# leo_BMS.net
KiCad netlist of a schematic drawn in Altium Designer
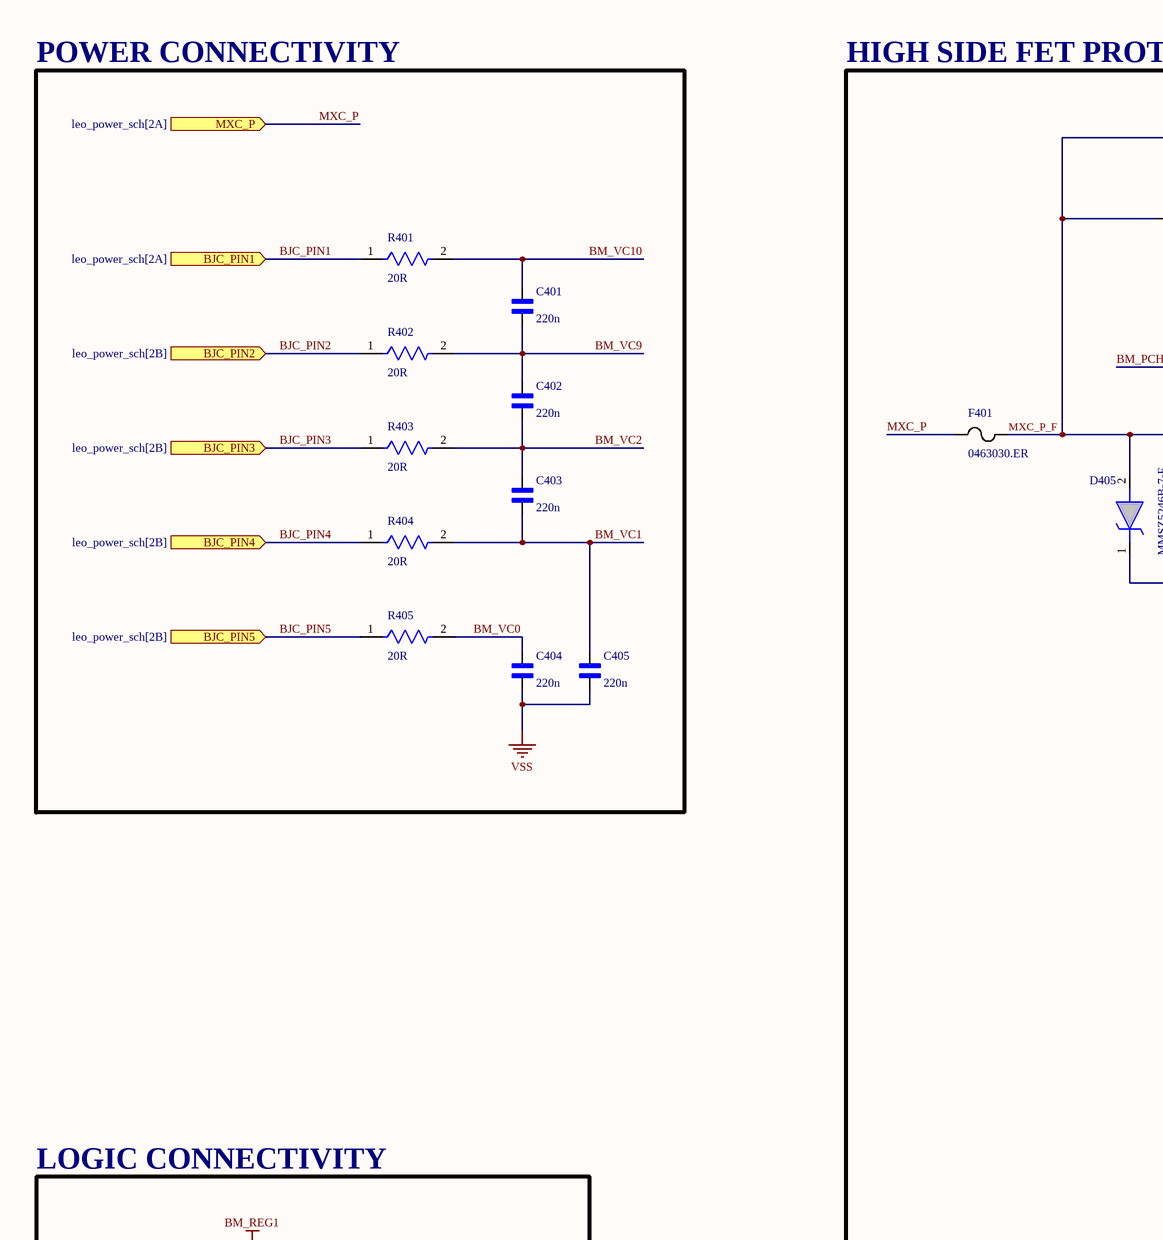
[diagram p0: leo_BMS.SchDoc, top left]
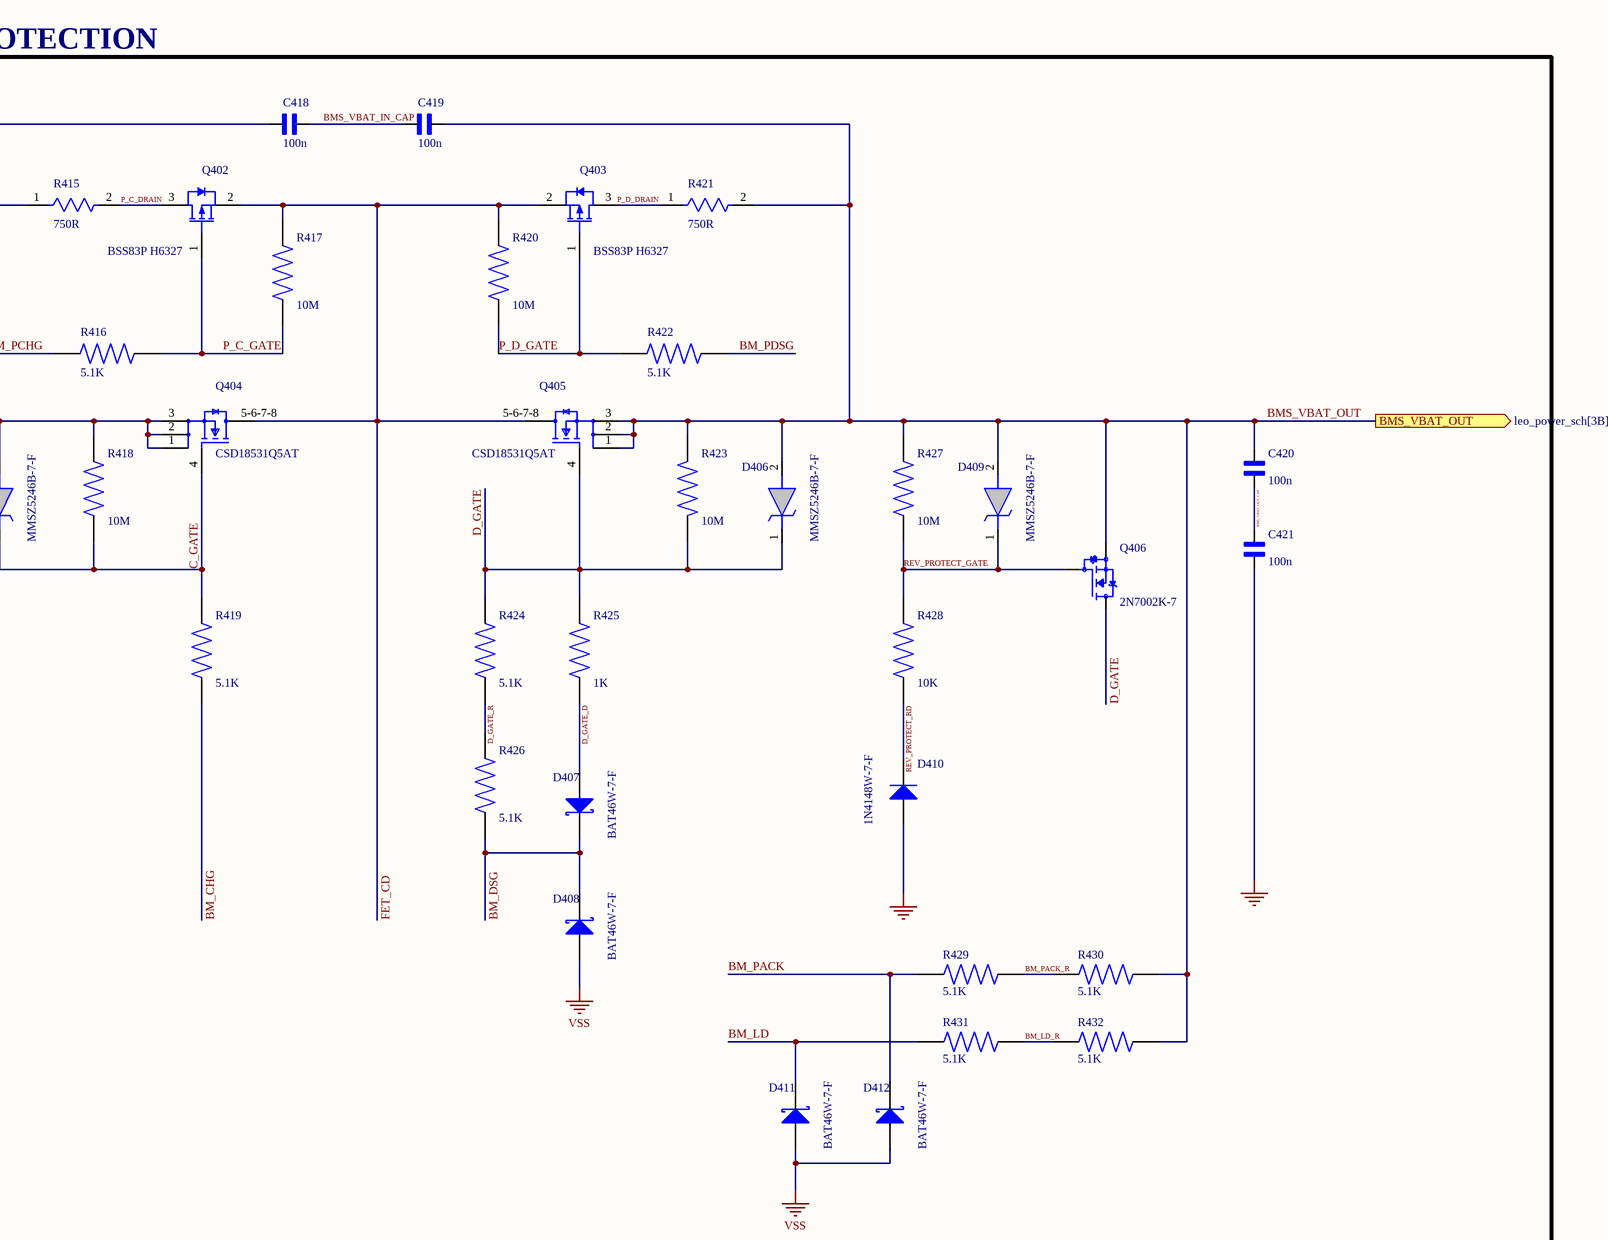
[diagram p1: leo_BMS.SchDoc, top right]
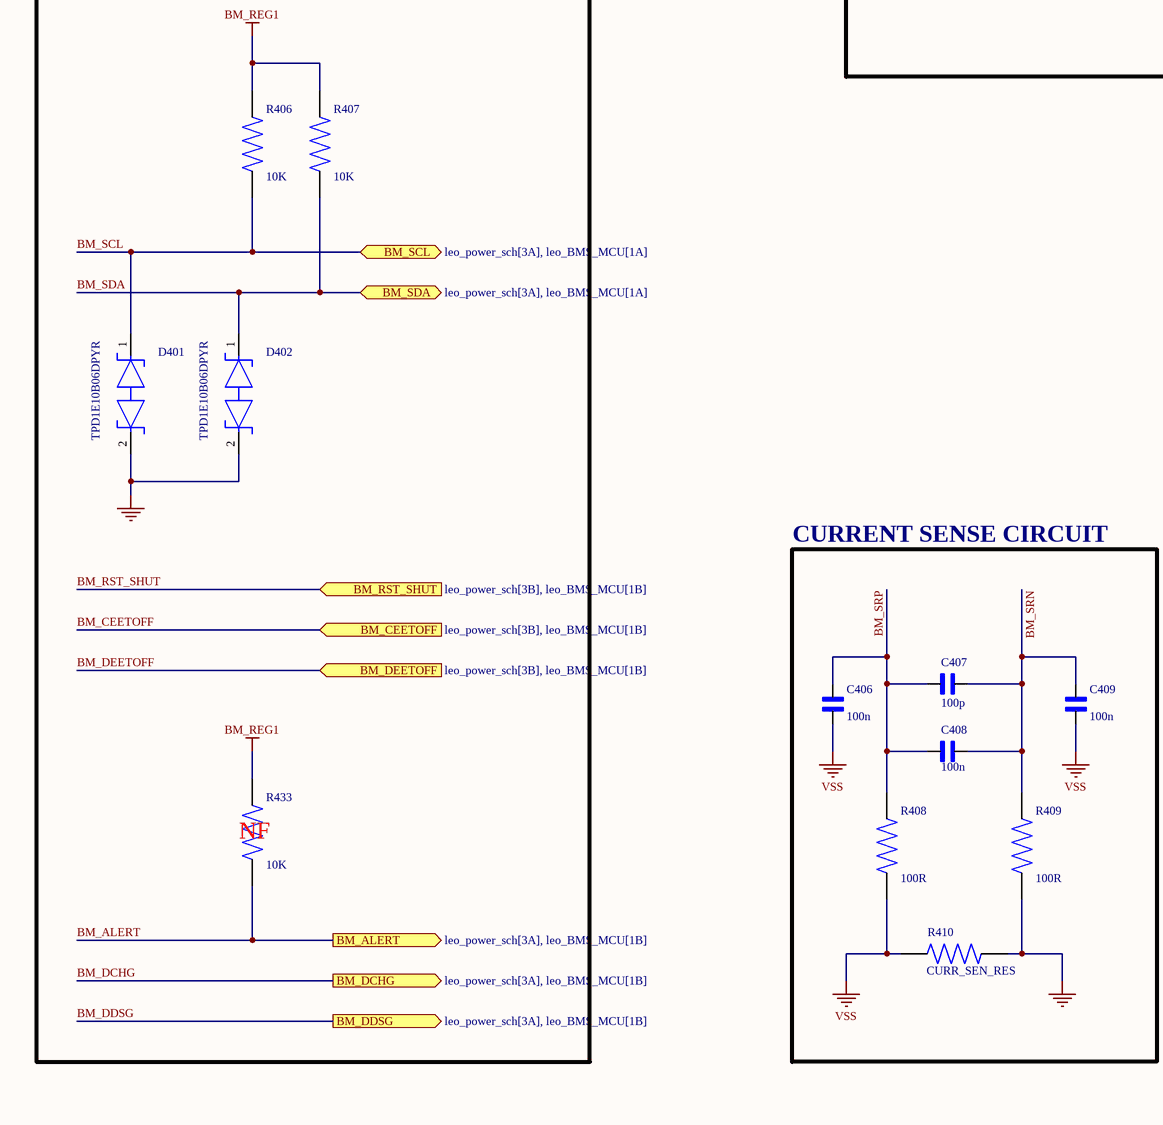
[diagram p2: leo_BMS.SchDoc, bottom left]
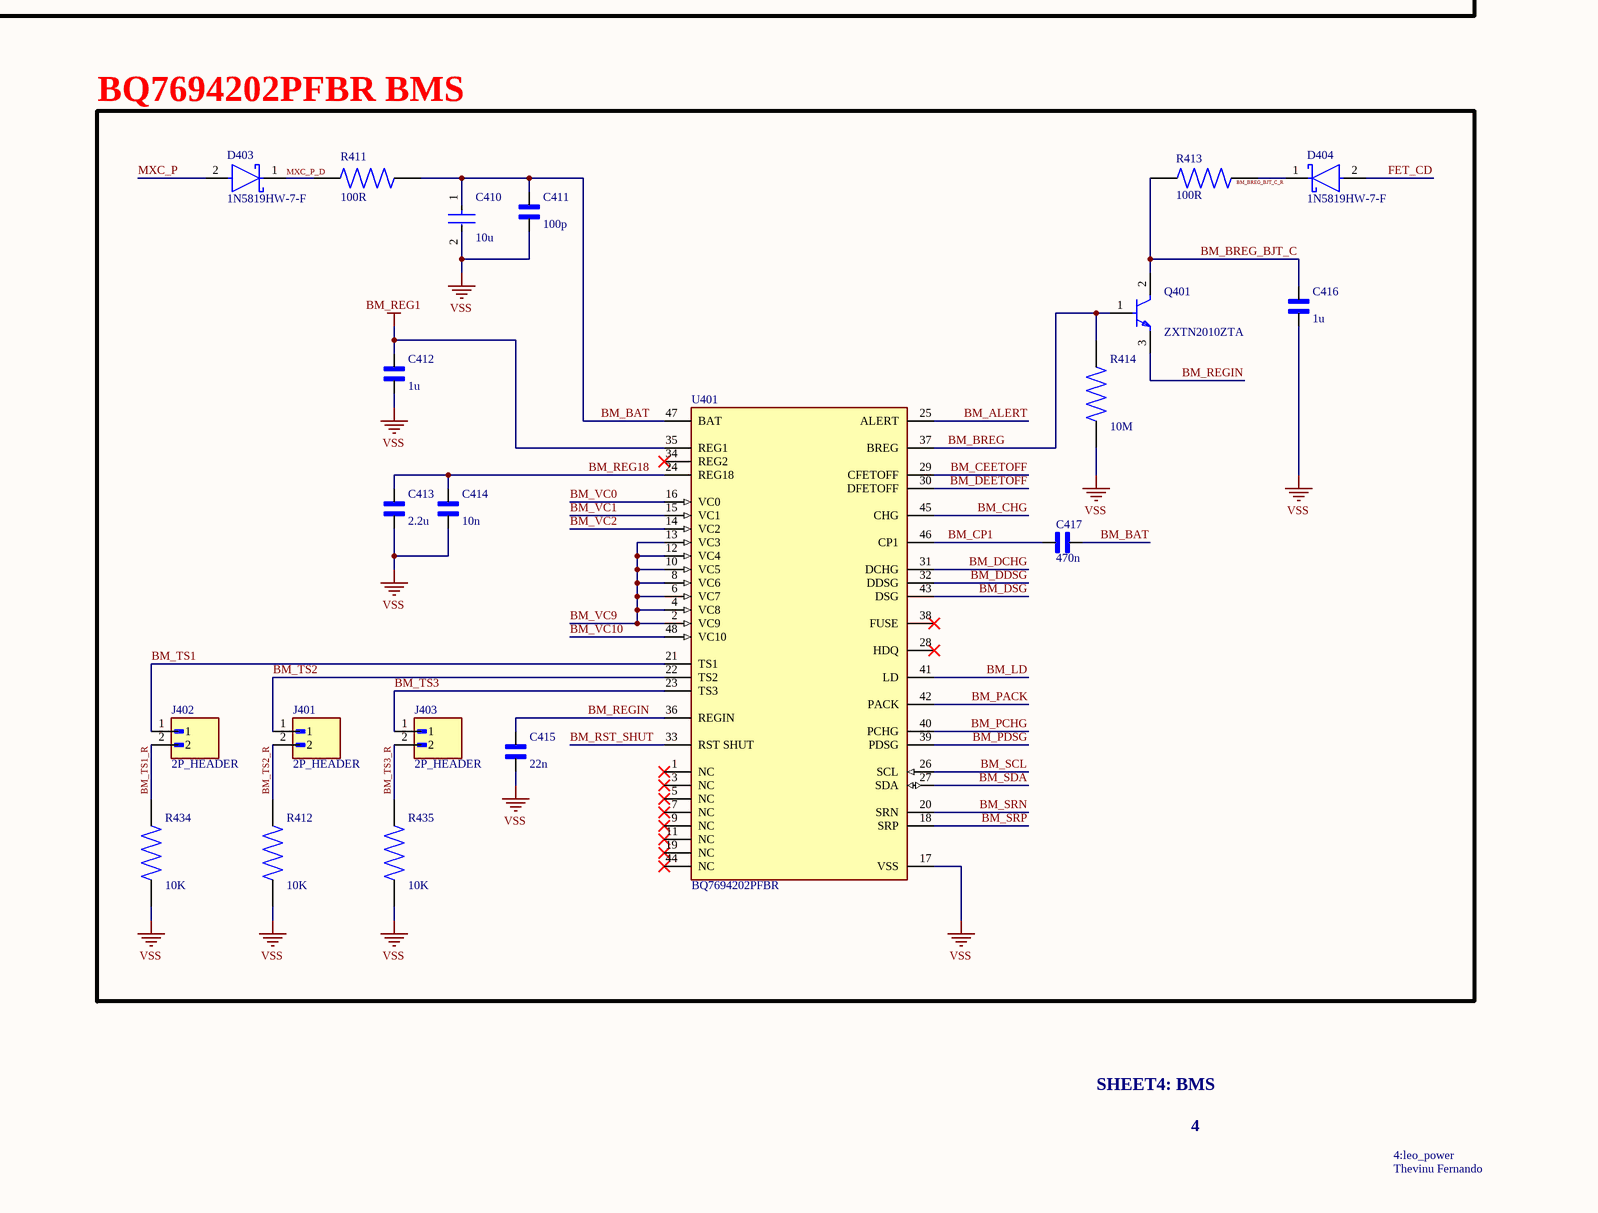
[diagram p3: leo_BMS.SchDoc, bottom right]

(export (version "E")
  (design (tool "Eeschema 10.0.6"))
  (components
    (comp (ref "C401")
      (value "220n")
      (footprint "CAP_0603")
      (description "Â±10% 50V Ceramic Capacitor X7R 0603 (1608 Metric)")
      (fields (field (name "MF") "Samsung Electro-Mechanics") (field (name "MP") "CL10B104KB8NNNC"))
      (libsource (lib "leo_power_schlib") (part "CAP_0603"))
    )
    (comp (ref "C402")
      (value "220n")
      (footprint "CAP_0603")
      (description "Â±10% 50V Ceramic Capacitor X7R 0603 (1608 Metric)")
      (fields (field (name "MF") "Samsung Electro-Mechanics") (field (name "MP") "CL10B104KB8NNNC"))
      (libsource (lib "leo_power_schlib") (part "CAP_0603"))
    )
    (comp (ref "C403")
      (value "220n")
      (footprint "CAP_0603")
      (description "Â±10% 50V Ceramic Capacitor X7R 0603 (1608 Metric)")
      (fields (field (name "MF") "Samsung Electro-Mechanics") (field (name "MP") "CL10B104KB8NNNC"))
      (libsource (lib "leo_power_schlib") (part "CAP_0603"))
    )
    (comp (ref "C404")
      (value "220n")
      (footprint "CAP_0603")
      (description "Â±10% 50V Ceramic Capacitor X7R 0603 (1608 Metric)")
      (fields (field (name "MF") "Samsung Electro-Mechanics") (field (name "MP") "CL10B104KB8NNNC"))
      (libsource (lib "leo_power_schlib") (part "CAP_0603"))
    )
    (comp (ref "C405")
      (value "220n")
      (footprint "CAP_0603")
      (description "Â±10% 50V Ceramic Capacitor X7R 0603 (1608 Metric)")
      (fields (field (name "MF") "Samsung Electro-Mechanics") (field (name "MP") "CL10B104KB8NNNC"))
      (libsource (lib "leo_power_schlib") (part "CAP_0603"))
    )
    (comp (ref "C406")
      (value "100n")
      (footprint "CAP_0402")
      (description "±10% 50V Ceramic Capacitor X7R 0402")
      (fields (field (name "MF") "Samsung") (field (name "MP") "CL05B104KO5NNNC"))
      (libsource (lib "leo_power_schlib") (part "CAP_0402"))
    )
    (comp (ref "C407")
      (value "100p")
      (footprint "CAP_0603")
      (description "Â±10% 50V Ceramic Capacitor X7R 0603 (1608 Metric)")
      (fields (field (name "MF") "Samsung Electro-Mechanics") (field (name "MP") "CL10B104KB8NNNC"))
      (libsource (lib "") (part "CAP_0603_1"))
    )
    (comp (ref "C408")
      (value "100n")
      (footprint "CAP_0603")
      (description "Â±10% 50V Ceramic Capacitor X7R 0603 (1608 Metric)")
      (fields (field (name "MF") "Samsung Electro-Mechanics") (field (name "MP") "CL10B104KB8NNNC"))
      (libsource (lib "") (part "CAP_0603_1"))
    )
    (comp (ref "C409")
      (value "100n")
      (footprint "CAP_0402")
      (description "±10% 50V Ceramic Capacitor X7R 0402")
      (fields (field (name "MF") "Samsung") (field (name "MP") "CL05B104KO5NNNC"))
      (libsource (lib "leo_power_schlib") (part "CAP_0402"))
    )
    (comp (ref "C410")
      (value "10u")
      (footprint "CAP_1206")
      (fields
        (field (name "MOUSER PART NUMBER") "187-CL31A226KAHNNNE")
        (field (name "PART NUMBER") "CL31A226KAHNNNE")
        (field (name "DIGIKEY PART NUMBER") "1276-3047-1-ND")
      )
      (libsource (lib "leo_power_schlib") (part "CAP_1206"))
    )
    (comp (ref "C411")
      (value "100p")
      (footprint "CAP_0603")
      (description "Â±10% 50V Ceramic Capacitor X7R 0603 (1608 Metric)")
      (fields (field (name "MF") "Samsung Electro-Mechanics") (field (name "MP") "CL10B104KB8NNNC"))
      (libsource (lib "leo_power_schlib") (part "CAP_0603"))
    )
    (comp (ref "C412")
      (value "1u")
      (footprint "CAP_0603")
      (description "Â±10% 50V Ceramic Capacitor X7R 0603 (1608 Metric)")
      (fields (field (name "MF") "Samsung Electro-Mechanics") (field (name "MP") "CL10B104KB8NNNC"))
      (libsource (lib "") (part "CAP_0603_2"))
    )
    (comp (ref "C413")
      (value "2.2u")
      (footprint "CAP_0603")
      (description "Â±10% 50V Ceramic Capacitor X7R 0603 (1608 Metric)")
      (fields (field (name "MF") "Samsung Electro-Mechanics") (field (name "MP") "CL10B104KB8NNNC"))
      (libsource (lib "leo_power_schlib") (part "CAP_0603"))
    )
    (comp (ref "C414")
      (value "10n")
      (footprint "CAP_0402")
      (description "±10% 50V Ceramic Capacitor X7R 0402")
      (fields (field (name "MF") "Samsung") (field (name "MP") "CL05B104KO5NNNC"))
      (libsource (lib "leo_power_schlib") (part "CAP_0402"))
    )
    (comp (ref "C415")
      (value "22n")
      (footprint "CAP_0402")
      (description "±10% 50V Ceramic Capacitor X7R 0402")
      (fields (field (name "MF") "Samsung") (field (name "MP") "CL05B104KO5NNNC"))
      (libsource (lib "leo_power_schlib") (part "CAP_0402"))
    )
    (comp (ref "C416")
      (value "1u")
      (footprint "CAP_0805")
      (description "Ceramic Capacitor X7R 0805 (2012 Metric)")
      (fields (field (name "MF") "Samsung Electro-Mechanics") (field (name "MP") "CL21B106KOQNNNE"))
      (libsource (lib "") (part "CAP_0805_1"))
    )
    (comp (ref "C417")
      (value "470n")
      (footprint "CAP_0805")
      (description "Ceramic Capacitor X7R 0805 (2012 Metric)")
      (fields (field (name "MF") "Samsung Electro-Mechanics") (field (name "MP") "CL21B106KOQNNNE"))
      (libsource (lib "leo_power_schlib") (part "CAP_0805"))
    )
    (comp (ref "C418")
      (value "100n")
      (footprint "CAP_0603")
      (description "Â±10% 50V Ceramic Capacitor X7R 0603 (1608 Metric)")
      (fields (field (name "MF") "Samsung Electro-Mechanics") (field (name "MP") "CL10B104KB8NNNC"))
      (libsource (lib "") (part "CAP_0603_1"))
    )
    (comp (ref "C419")
      (value "100n")
      (footprint "CAP_0603")
      (description "Â±10% 50V Ceramic Capacitor X7R 0603 (1608 Metric)")
      (fields (field (name "MF") "Samsung Electro-Mechanics") (field (name "MP") "CL10B104KB8NNNC"))
      (libsource (lib "") (part "CAP_0603_1"))
    )
    (comp (ref "C420")
      (value "100n")
      (footprint "CAP_0603")
      (description "Â±10% 50V Ceramic Capacitor X7R 0603 (1608 Metric)")
      (fields (field (name "MF") "Samsung Electro-Mechanics") (field (name "MP") "CL10B104KB8NNNC"))
      (libsource (lib "leo_power_schlib") (part "CAP_0603"))
    )
    (comp (ref "C421")
      (value "100n")
      (footprint "CAP_0603")
      (description "Â±10% 50V Ceramic Capacitor X7R 0603 (1608 Metric)")
      (fields (field (name "MF") "Samsung Electro-Mechanics") (field (name "MP") "CL10B104KB8NNNC"))
      (libsource (lib "leo_power_schlib") (part "CAP_0603"))
    )
    (comp (ref "D401")
      (value "TPD1E10B06DPYR")
      (footprint "FP-DPY0002A-MFG")
      (description "TVS DIODE 5.5V 14V 2X1SON")
      (libsource (lib "leo_power_schlib") (part "TPD1E10B06DPYR"))
    )
    (comp (ref "D402")
      (value "TPD1E10B06DPYR")
      (footprint "FP-DPY0002A-MFG")
      (description "TVS DIODE 5.5V 14V 2X1SON")
      (libsource (lib "leo_power_schlib") (part "TPD1E10B06DPYR"))
    )
    (comp (ref "D403")
      (value "1N5819HW-7-F")
      (footprint "FP-SOD123-MFG")
      (description "DIODE SCHOTTKY 40V 1A SOD123")
      (libsource (lib "leo_power_schlib") (part "1N5819HW-7-F"))
    )
    (comp (ref "D404")
      (value "1N5819HW-7-F")
      (footprint "FP-SOD123-MFG")
      (description "DIODE SCHOTTKY 40V 1A SOD123")
      (libsource (lib "leo_power_schlib") (part "1N5819HW-7-F"))
    )
    (comp (ref "D405")
      (value "MMSZ5246B-7-F")
      (footprint "SOD123_DIO")
      (description "Diodes Inc MMSZ5246B-7-F Zener Diode, 16V 5% 500 mW SMT 2-Pin SOD-123")
      (fields (field (name "MOUSER PART NUMBER") "621-MMSZ5246B-F"))
      (libsource (lib "leo_power_schlib") (part "MMSZ5246B-7-F"))
    )
    (comp (ref "D406")
      (value "MMSZ5246B-7-F")
      (footprint "SOD123_DIO")
      (description "Diodes Inc MMSZ5246B-7-F Zener Diode, 16V 5% 500 mW SMT 2-Pin SOD-123")
      (fields (field (name "MOUSER PART NUMBER") "621-MMSZ5246B-F"))
      (libsource (lib "leo_power_schlib") (part "MMSZ5246B-7-F"))
    )
    (comp (ref "D407")
      (value "BAT46W-7-F")
      (footprint "DIOD-SOD-123-2_V")
      (description "Surface Mount Schottky Barrier Diode, 100 V, -55 to 125 degC, 2-Pin SOD123, RoHS, Tape and Reel")
      (fields (field (name "MANUFACTURER") "Diodes Inc"))
      (libsource (lib "leo_power_schlib") (part "BAT46W-7-F"))
    )
    (comp (ref "D408")
      (value "BAT46W-7-F")
      (footprint "DIOD-SOD-123-2_V")
      (description "Surface Mount Schottky Barrier Diode, 100 V, -55 to 125 degC, 2-Pin SOD123, RoHS, Tape and Reel")
      (fields (field (name "MANUFACTURER") "Diodes Inc"))
      (libsource (lib "leo_power_schlib") (part "BAT46W-7-F"))
    )
    (comp (ref "D409")
      (value "MMSZ5246B-7-F")
      (footprint "SOD123_DIO")
      (description "Diodes Inc MMSZ5246B-7-F Zener Diode, 16V 5% 500 mW SMT 2-Pin SOD-123")
      (fields (field (name "MOUSER PART NUMBER") "621-MMSZ5246B-F"))
      (libsource (lib "leo_power_schlib") (part "MMSZ5246B-7-F"))
    )
    (comp (ref "D410")
      (value "1N4148W-7-F")
      (footprint "DIOD-SOD123-2_V")
      (description "Fast Switching Diode, 100 V, 0.15 A, -65 to 150 degC, 2-Pin?SOD123, RoHS, Tape and Reel")
      (fields (field (name "MANUFACTURER") "DiodesIncorporated"))
      (libsource (lib "leo_power_schlib") (part "1N4148W-7-F"))
    )
    (comp (ref "D411")
      (value "BAT46W-7-F")
      (footprint "DIOD-SOD-123-2_V")
      (description "Surface Mount Schottky Barrier Diode, 100 V, -55 to 125 degC, 2-Pin SOD123, RoHS, Tape and Reel")
      (fields (field (name "MANUFACTURER") "Diodes Inc"))
      (libsource (lib "leo_power_schlib") (part "BAT46W-7-F"))
    )
    (comp (ref "D412")
      (value "BAT46W-7-F")
      (footprint "DIOD-SOD-123-2_V")
      (description "Surface Mount Schottky Barrier Diode, 100 V, -55 to 125 degC, 2-Pin SOD123, RoHS, Tape and Reel")
      (fields (field (name "MANUFACTURER") "Diodes Inc"))
      (libsource (lib "leo_power_schlib") (part "BAT46W-7-F"))
    )
    (comp (ref "F401")
      (value "0463030.ER")
      (footprint "FUSE_0463_LTF-M")
      (description "Littelfuse 30A FF Non-Resettable Surface Mount Fuse, 250V")
      (fields (field (name "COPYRIGHT") "Copyright (C) 2025 Ultra Librarian. All rights reserved."))
      (libsource (lib "leo_power_schlib") (part "0463030.ER"))
    )
    (comp (ref "J401")
      (value "2P_HEADER")
      (footprint "HARWIN_M20-9990246 2P Header")
      (description "2.54mm (0.1) Pitch SIL Vertical Throughboard Pin Header, 6.1mm mating pin height, tin, 2 contacts")
      (fields (field (name "MF") "Harwin") (field (name "MP") "M20-9990246"))
      (libsource (lib "leo_power_schlib") (part "2P_HEADER"))
    )
    (comp (ref "J402")
      (value "2P_HEADER")
      (footprint "HARWIN_M20-9990246 2P Header")
      (description "2.54mm (0.1) Pitch SIL Vertical Throughboard Pin Header, 6.1mm mating pin height, tin, 2 contacts")
      (fields (field (name "MF") "Harwin") (field (name "MP") "M20-9990246"))
      (libsource (lib "leo_power_schlib") (part "2P_HEADER"))
    )
    (comp (ref "J403")
      (value "2P_HEADER")
      (footprint "HARWIN_M20-9990246 2P Header")
      (description "2.54mm (0.1) Pitch SIL Vertical Throughboard Pin Header, 6.1mm mating pin height, tin, 2 contacts")
      (fields (field (name "MF") "Harwin") (field (name "MP") "M20-9990246"))
      (libsource (lib "leo_power_schlib") (part "2P_HEADER"))
    )
    (comp (ref "Q401")
      (value "ZXTN2010ZTA")
      (footprint "FP-SOT89-MFG")
      (description "TRANS NPN 60V 5A SOT89")
      (fields
        (field (name "OCTOPART") "https://octopart.com/zxtn2010zta-diodes+inc.-360166")
        (field (name "MANUFACTURER") "Diodes Inc.")
      )
      (libsource (lib "leo_power_schlib") (part "ZXTN2010ZTA"))
    )
    (comp (ref "Q402")
      (value "BSS83P H6327")
      (footprint "INF-SOT23_N")
      (description "SIPMOS(R) Small-Signal-Transistor, -0.33 A, 2 Ohm, -60 V, 3-Pin SOT-23, RoHS, Tape and Reel")
      (fields (field (name "MANUFACTURER") "Infineon"))
      (libsource (lib "leo_power_schlib") (part "BSS83PH6327"))
    )
    (comp (ref "Q403")
      (value "BSS83P H6327")
      (footprint "INF-SOT23_N")
      (description "SIPMOS(R) Small-Signal-Transistor, -0.33 A, 2 Ohm, -60 V, 3-Pin SOT-23, RoHS, Tape and Reel")
      (fields (field (name "MANUFACTURER") "Infineon"))
      (libsource (lib "leo_power_schlib") (part "BSS83PH6327"))
    )
    (comp (ref "Q404")
      (value "CSD18531Q5AT")
      (footprint "FP-DQJ0008A-MFG")
      (description "MOSFET N-CH 60V 100A 8VSON")
      (libsource (lib "leo_power_schlib") (part "CSD18531Q5A"))
    )
    (comp (ref "Q405")
      (value "CSD18531Q5AT")
      (footprint "FP-DQJ0008A-MFG")
      (description "MOSFET N-CH 60V 100A 8VSON")
      (libsource (lib "leo_power_schlib") (part "CSD18531Q5A"))
    )
    (comp (ref "Q406")
      (value "2N7002K-7")
      (footprint "SOT91P240X110-3N")
      (description "2N7002K Series 60 V 2 Ohm SMT N-Channel Enhancement Mode Mosfet - SOT-23-3")
      (fields (field (name "MF") "{'manufacturer': u'Diodes Incorporated'}"))
      (libsource (lib "leo_power_schlib") (part "2N7002K-7"))
    )
    (comp (ref "R401")
      (value "20R")
      (footprint "RES_1210")
      (description "RES SMD 205K OHM 1% 1/2W 1663")
      (fields (field (name "TOLERANCE") "1%"))
      (libsource (lib "leo_power_schlib") (part "RES_1210"))
    )
    (comp (ref "R402")
      (value "20R")
      (footprint "RES_1210")
      (description "RES SMD 205K OHM 1% 1/2W 1663")
      (fields (field (name "TOLERANCE") "1%"))
      (libsource (lib "leo_power_schlib") (part "RES_1210"))
    )
    (comp (ref "R403")
      (value "20R")
      (footprint "RES_1210")
      (description "RES SMD 205K OHM 1% 1/2W 1663")
      (fields (field (name "TOLERANCE") "1%"))
      (libsource (lib "leo_power_schlib") (part "RES_1210"))
    )
    (comp (ref "R404")
      (value "20R")
      (footprint "RES_1210")
      (description "RES SMD 205K OHM 1% 1/2W 1663")
      (fields (field (name "TOLERANCE") "1%"))
      (libsource (lib "leo_power_schlib") (part "RES_1210"))
    )
    (comp (ref "R405")
      (value "20R")
      (footprint "RES_1210")
      (description "RES SMD 205K OHM 1% 1/2W 1663")
      (fields (field (name "TOLERANCE") "1%"))
      (libsource (lib "leo_power_schlib") (part "RES_1210"))
    )
    (comp (ref "R406")
      (value "10K")
      (footprint "RES_0402")
      (description "Chip Resistor 0402 (1005 Metric) Automotive AEC-Q200 Thick Film")
      (fields (field (name "MF") "Panasonic") (field (name "MP") "ERJ-2RKF1002X"))
      (libsource (lib "leo_power_schlib") (part "RES_0402"))
    )
    (comp (ref "R407")
      (value "10K")
      (footprint "RES_0402")
      (description "Chip Resistor 0402 (1005 Metric) Automotive AEC-Q200 Thick Film")
      (fields (field (name "MF") "Panasonic") (field (name "MP") "ERJ-2RKF1002X"))
      (libsource (lib "leo_power_schlib") (part "RES_0402"))
    )
    (comp (ref "R408")
      (value "100R")
      (footprint "RES_0603")
      (description "Â±1% 0.1W, 1/10W Chip Resistor 0603 (1608 Metric) Moisture Resistant Thick Film")
      (fields (field (name "MF") "Yageo") (field (name "MP") "RC0603FR-0791KL"))
      (libsource (lib "leo_power_schlib") (part "RES_0603"))
    )
    (comp (ref "R409")
      (value "100R")
      (footprint "RES_0603")
      (description "Â±1% 0.1W, 1/10W Chip Resistor 0603 (1608 Metric) Moisture Resistant Thick Film")
      (fields (field (name "MF") "Yageo") (field (name "MP") "RC0603FR-0791KL"))
      (libsource (lib "leo_power_schlib") (part "RES_0603"))
    )
    (comp (ref "R410")
      (value "CURR_SEN_RES")
      (footprint "CURR_SEN_RES")
      (description "Resistor, Metal Strip, Res 0.001 Ohms, Pwr-Trg 3 W, Tol 1%, SMD ¦ Bourns CRE2512-FZ-R001E-3")
      (fields (field (name "MF") "Bourns Inc.") (field (name "MP") "CRE2512-FZ-R001E-3"))
      (libsource (lib "leo_power_schlib") (part "CURR_SEN_RES"))
    )
    (comp (ref "R411")
      (value "100R")
      (footprint "RES_2512")
      (fields (field (name "MF") "Vishay Dale") (field (name "MP") "CRCW2512100RFKEG"))
      (libsource (lib "leo_power_schlib") (part "RES_2512"))
    )
    (comp (ref "R412")
      (value "10K")
      (footprint "RES_0402")
      (description "Chip Resistor 0402 (1005 Metric) Automotive AEC-Q200 Thick Film")
      (fields (field (name "MF") "Panasonic") (field (name "MP") "ERJ-2RKF1002X"))
      (libsource (lib "leo_power_schlib") (part "RES_0402"))
    )
    (comp (ref "R413")
      (value "100R")
      (footprint "RES_2512")
      (fields (field (name "MF") "Vishay Dale") (field (name "MP") "CRCW2512100RFKEG"))
      (libsource (lib "leo_power_schlib") (part "RES_2512"))
    )
    (comp (ref "R414")
      (value "10M")
      (footprint "RES_0402")
      (description "Chip Resistor 0402 (1005 Metric) Automotive AEC-Q200 Thick Film")
      (fields (field (name "MF") "Panasonic") (field (name "MP") "ERJ-2RKF1002X"))
      (libsource (lib "leo_power_schlib") (part "RES_0402"))
    )
    (comp (ref "R415")
      (value "750R")
      (footprint "RES_1210")
      (description "RES SMD 205K OHM 1% 1/2W 1663")
      (fields (field (name "TOLERANCE") "1%"))
      (libsource (lib "leo_power_schlib") (part "RES_1210"))
    )
    (comp (ref "R416")
      (value "5.1K")
      (footprint "RES_0603")
      (description "Â±1% 0.1W, 1/10W Chip Resistor 0603 (1608 Metric) Moisture Resistant Thick Film")
      (fields (field (name "MF") "Yageo") (field (name "MP") "RC0603FR-0791KL"))
      (libsource (lib "leo_power_schlib") (part "RES_0603"))
    )
    (comp (ref "R417")
      (value "10M")
      (footprint "RES_0603")
      (description "Â±1% 0.1W, 1/10W Chip Resistor 0603 (1608 Metric) Moisture Resistant Thick Film")
      (fields (field (name "MF") "Yageo") (field (name "MP") "RC0603FR-0791KL"))
      (libsource (lib "leo_power_schlib") (part "RES_0603"))
    )
    (comp (ref "R418")
      (value "10M")
      (footprint "RES_0603")
      (description "Â±1% 0.1W, 1/10W Chip Resistor 0603 (1608 Metric) Moisture Resistant Thick Film")
      (fields (field (name "MF") "Yageo") (field (name "MP") "RC0603FR-0791KL"))
      (libsource (lib "leo_power_schlib") (part "RES_0603"))
    )
    (comp (ref "R419")
      (value "5.1K")
      (footprint "RES_0603")
      (description "Â±1% 0.1W, 1/10W Chip Resistor 0603 (1608 Metric) Moisture Resistant Thick Film")
      (fields (field (name "MF") "Yageo") (field (name "MP") "RC0603FR-0791KL"))
      (libsource (lib "leo_power_schlib") (part "RES_0603"))
    )
    (comp (ref "R420")
      (value "10M")
      (footprint "RES_0603")
      (description "Â±1% 0.1W, 1/10W Chip Resistor 0603 (1608 Metric) Moisture Resistant Thick Film")
      (fields (field (name "MF") "Yageo") (field (name "MP") "RC0603FR-0791KL"))
      (libsource (lib "leo_power_schlib") (part "RES_0603"))
    )
    (comp (ref "R421")
      (value "750R")
      (footprint "RES_1210")
      (description "RES SMD 205K OHM 1% 1/2W 1663")
      (fields (field (name "TOLERANCE") "1%"))
      (libsource (lib "leo_power_schlib") (part "RES_1210"))
    )
    (comp (ref "R422")
      (value "5.1K")
      (footprint "RES_0603")
      (description "Â±1% 0.1W, 1/10W Chip Resistor 0603 (1608 Metric) Moisture Resistant Thick Film")
      (fields (field (name "MF") "Yageo") (field (name "MP") "RC0603FR-0791KL"))
      (libsource (lib "leo_power_schlib") (part "RES_0603"))
    )
    (comp (ref "R423")
      (value "10M")
      (footprint "RES_0603")
      (description "Â±1% 0.1W, 1/10W Chip Resistor 0603 (1608 Metric) Moisture Resistant Thick Film")
      (fields (field (name "MF") "Yageo") (field (name "MP") "RC0603FR-0791KL"))
      (libsource (lib "leo_power_schlib") (part "RES_0603"))
    )
    (comp (ref "R424")
      (value "5.1K")
      (footprint "RES_0603")
      (description "Â±1% 0.1W, 1/10W Chip Resistor 0603 (1608 Metric) Moisture Resistant Thick Film")
      (fields (field (name "MF") "Yageo") (field (name "MP") "RC0603FR-0791KL"))
      (libsource (lib "leo_power_schlib") (part "RES_0603"))
    )
    (comp (ref "R425")
      (value "1K")
      (footprint "RES_0603")
      (description "Â±1% 0.1W, 1/10W Chip Resistor 0603 (1608 Metric) Moisture Resistant Thick Film")
      (fields (field (name "MF") "Yageo") (field (name "MP") "RC0603FR-0791KL"))
      (libsource (lib "leo_power_schlib") (part "RES_0603"))
    )
    (comp (ref "R426")
      (value "5.1K")
      (footprint "RES_0603")
      (description "Â±1% 0.1W, 1/10W Chip Resistor 0603 (1608 Metric) Moisture Resistant Thick Film")
      (fields (field (name "MF") "Yageo") (field (name "MP") "RC0603FR-0791KL"))
      (libsource (lib "leo_power_schlib") (part "RES_0603"))
    )
    (comp (ref "R427")
      (value "10M")
      (footprint "RES_0603")
      (description "Â±1% 0.1W, 1/10W Chip Resistor 0603 (1608 Metric) Moisture Resistant Thick Film")
      (fields (field (name "MF") "Yageo") (field (name "MP") "RC0603FR-0791KL"))
      (libsource (lib "leo_power_schlib") (part "RES_0603"))
    )
    (comp (ref "R428")
      (value "10K")
      (footprint "RES_0603")
      (description "Â±1% 0.1W, 1/10W Chip Resistor 0603 (1608 Metric) Moisture Resistant Thick Film")
      (fields (field (name "MF") "Yageo") (field (name "MP") "RC0603FR-0791KL"))
      (libsource (lib "leo_power_schlib") (part "RES_0603"))
    )
    (comp (ref "R429")
      (value "5.1K")
      (footprint "RES_0603")
      (description "Â±1% 0.1W, 1/10W Chip Resistor 0603 (1608 Metric) Moisture Resistant Thick Film")
      (fields (field (name "MF") "Yageo") (field (name "MP") "RC0603FR-0791KL"))
      (libsource (lib "leo_power_schlib") (part "RES_0603"))
    )
    (comp (ref "R430")
      (value "5.1K")
      (footprint "RES_0603")
      (description "Â±1% 0.1W, 1/10W Chip Resistor 0603 (1608 Metric) Moisture Resistant Thick Film")
      (fields (field (name "MF") "Yageo") (field (name "MP") "RC0603FR-0791KL"))
      (libsource (lib "leo_power_schlib") (part "RES_0603"))
    )
    (comp (ref "R431")
      (value "5.1K")
      (footprint "RES_0603")
      (description "Â±1% 0.1W, 1/10W Chip Resistor 0603 (1608 Metric) Moisture Resistant Thick Film")
      (fields (field (name "MF") "Yageo") (field (name "MP") "RC0603FR-0791KL"))
      (libsource (lib "leo_power_schlib") (part "RES_0603"))
    )
    (comp (ref "R432")
      (value "5.1K")
      (footprint "RES_0603")
      (description "Â±1% 0.1W, 1/10W Chip Resistor 0603 (1608 Metric) Moisture Resistant Thick Film")
      (fields (field (name "MF") "Yageo") (field (name "MP") "RC0603FR-0791KL"))
      (libsource (lib "leo_power_schlib") (part "RES_0603"))
    )
    (comp (ref "R433")
      (value "10K")
      (footprint "RES_0402")
      (description "Chip Resistor 0402 (1005 Metric) Automotive AEC-Q200 Thick Film")
      (fields (field (name "MF") "Panasonic") (field (name "MP") "ERJ-2RKF1002X"))
      (libsource (lib "leo_power_schlib") (part "RES_0402"))
    )
    (comp (ref "R434")
      (value "10K")
      (footprint "RES_0402")
      (description "Chip Resistor 0402 (1005 Metric) Automotive AEC-Q200 Thick Film")
      (fields (field (name "MF") "Panasonic") (field (name "MP") "ERJ-2RKF1002X"))
      (libsource (lib "leo_power_schlib") (part "RES_0402"))
    )
    (comp (ref "R435")
      (value "10K")
      (footprint "RES_0402")
      (description "Chip Resistor 0402 (1005 Metric) Automotive AEC-Q200 Thick Film")
      (fields (field (name "MF") "Panasonic") (field (name "MP") "ERJ-2RKF1002X"))
      (libsource (lib "leo_power_schlib") (part "RES_0402"))
    )
    (comp (ref "U401")
      (value "BQ7694202PFBR")
      (footprint "FP-PFB0048A-IPC_B")
      (libsource (lib "leo_power_schlib") (part "BQ7694202PFBR"))
    )
  )
  (nets
    (net (code "1") (name "/BJC_PIN1") (class "Default")
      (node (ref "R401") (pin "1") (pinfunction "1_1") (pintype "passive"))
    )
    (net (code "2") (name "/BJC_PIN2") (class "Default")
      (node (ref "R402") (pin "1") (pinfunction "1_1") (pintype "passive"))
    )
    (net (code "3") (name "/BJC_PIN3") (class "Default")
      (node (ref "R403") (pin "1") (pinfunction "1_1") (pintype "passive"))
    )
    (net (code "4") (name "/BJC_PIN4") (class "Default")
      (node (ref "R404") (pin "1") (pinfunction "1_1") (pintype "passive"))
    )
    (net (code "5") (name "/BJC_PIN5") (class "Default")
      (node (ref "R405") (pin "1") (pinfunction "1_1") (pintype "passive"))
    )
    (net (code "6") (name "/BMS_VBAT_IN_CAP") (class "Default")
      (node (ref "C418") (pin "2") (pinfunction "2_2") (pintype "passive"))
      (node (ref "C419") (pin "1") (pinfunction "1_1") (pintype "passive"))
    )
    (net (code "7") (name "/BMS_VBAT_OUT") (class "Default")
      (node (ref "C419") (pin "2") (pinfunction "2_2") (pintype "passive"))
      (node (ref "C420") (pin "2") (pinfunction "2_2") (pintype "passive"))
      (node (ref "D406") (pin "2") (pinfunction "A_2") (pintype "passive"))
      (node (ref "D409") (pin "2") (pinfunction "A_2") (pintype "passive"))
      (node (ref "Q405") (pin "1") (pinfunction "S_1") (pintype "passive"))
      (node (ref "Q405") (pin "2") (pinfunction "S_2") (pintype "passive"))
      (node (ref "Q405") (pin "3") (pinfunction "S_3") (pintype "passive"))
      (node (ref "Q406") (pin "2") (pinfunction "S_2") (pintype "passive"))
      (node (ref "R421") (pin "2") (pinfunction "2_2") (pintype "passive"))
      (node (ref "R423") (pin "2") (pinfunction "2_2") (pintype "passive"))
      (node (ref "R427") (pin "2") (pinfunction "2_2") (pintype "passive"))
      (node (ref "R430") (pin "1") (pinfunction "1_1") (pintype "passive"))
      (node (ref "R432") (pin "1") (pinfunction "1_1") (pintype "passive"))
    )
    (net (code "8") (name "/BMS_VBAT_OUT_CAP") (class "Default")
      (node (ref "C420") (pin "1") (pinfunction "1_1") (pintype "passive"))
      (node (ref "C421") (pin "2") (pinfunction "2_2") (pintype "passive"))
    )
    (net (code "9") (name "/BM_ALERT") (class "Default")
      (node (ref "R433") (pin "1") (pinfunction "1_1") (pintype "passive"))
      (node (ref "U401") (pin "25") (pinfunction "ALERT_25") (pintype "passive"))
    )
    (net (code "10") (name "/BM_BAT") (class "Default")
      (node (ref "C410") (pin "1") (pinfunction "1_1") (pintype "passive"))
      (node (ref "C411") (pin "2") (pinfunction "2_2") (pintype "passive"))
      (node (ref "C417") (pin "2") (pinfunction "2_2") (pintype "passive"))
      (node (ref "R411") (pin "2") (pinfunction "2_2") (pintype "passive"))
      (node (ref "U401") (pin "47") (pinfunction "BAT_47") (pintype "power_in"))
    )
    (net (code "11") (name "/BM_BREG") (class "Default")
      (node (ref "Q401") (pin "1") (pinfunction "B_1") (pintype "passive"))
      (node (ref "R414") (pin "2") (pinfunction "2_2") (pintype "passive"))
      (node (ref "U401") (pin "37") (pinfunction "BREG_37") (pintype "passive"))
    )
    (net (code "12") (name "/BM_BREG_BJT_C") (class "Default")
      (node (ref "C416") (pin "1") (pinfunction "1_1") (pintype "passive"))
      (node (ref "Q401") (pin "2") (pinfunction "C_2") (pintype "passive"))
      (node (ref "R413") (pin "1") (pinfunction "1_1") (pintype "passive"))
    )
    (net (code "13") (name "/BM_BREG_BJT_C_R") (class "Default")
      (node (ref "D404") (pin "1") (pinfunction "C_1") (pintype "passive"))
      (node (ref "R413") (pin "2") (pinfunction "2_2") (pintype "passive"))
    )
    (net (code "14") (name "/BM_CEETOFF") (class "Default")
      (node (ref "U401") (pin "29") (pinfunction "CFETOFF_29") (pintype "passive"))
    )
    (net (code "15") (name "/BM_CHG") (class "Default")
      (node (ref "R419") (pin "1") (pinfunction "1_1") (pintype "passive"))
      (node (ref "U401") (pin "45") (pinfunction "CHG_45") (pintype "passive"))
    )
    (net (code "16") (name "/BM_CP1") (class "Default")
      (node (ref "C417") (pin "1") (pinfunction "1_1") (pintype "passive"))
      (node (ref "U401") (pin "46") (pinfunction "CP1_46") (pintype "passive"))
    )
    (net (code "17") (name "/BM_DCHG") (class "Default")
      (node (ref "U401") (pin "31") (pinfunction "DCHG_31") (pintype "passive"))
    )
    (net (code "18") (name "/BM_DDSG") (class "Default")
      (node (ref "U401") (pin "32") (pinfunction "DDSG_32") (pintype "passive"))
    )
    (net (code "19") (name "/BM_DEETOFF") (class "Default")
      (node (ref "U401") (pin "30") (pinfunction "DFETOFF_30") (pintype "passive"))
    )
    (net (code "20") (name "/BM_DSG") (class "Default")
      (node (ref "D407") (pin "2") (pinfunction "K_2") (pintype "passive"))
      (node (ref "D408") (pin "2") (pinfunction "K_2") (pintype "passive"))
      (node (ref "R426") (pin "1") (pinfunction "1_1") (pintype "passive"))
      (node (ref "U401") (pin "43") (pinfunction "DSG_43") (pintype "passive"))
    )
    (net (code "21") (name "/BM_LD") (class "Default")
      (node (ref "D411") (pin "2") (pinfunction "K_2") (pintype "passive"))
      (node (ref "R431") (pin "2") (pinfunction "2_2") (pintype "passive"))
      (node (ref "U401") (pin "41") (pinfunction "LD_41") (pintype "passive"))
    )
    (net (code "22") (name "/BM_LD_R") (class "Default")
      (node (ref "R431") (pin "1") (pinfunction "1_1") (pintype "passive"))
      (node (ref "R432") (pin "2") (pinfunction "2_2") (pintype "passive"))
    )
    (net (code "23") (name "/BM_PACK") (class "Default")
      (node (ref "D412") (pin "2") (pinfunction "K_2") (pintype "passive"))
      (node (ref "R429") (pin "2") (pinfunction "2_2") (pintype "passive"))
      (node (ref "U401") (pin "42") (pinfunction "PACK_42") (pintype "passive"))
    )
    (net (code "24") (name "/BM_PACK_R") (class "Default")
      (node (ref "R429") (pin "1") (pinfunction "1_1") (pintype "passive"))
      (node (ref "R430") (pin "2") (pinfunction "2_2") (pintype "passive"))
    )
    (net (code "25") (name "/BM_PCHG") (class "Default")
      (node (ref "R416") (pin "2") (pinfunction "2_2") (pintype "passive"))
      (node (ref "U401") (pin "40") (pinfunction "PCHG_40") (pintype "passive"))
    )
    (net (code "26") (name "/BM_PDSG") (class "Default")
      (node (ref "R422") (pin "1") (pinfunction "1_1") (pintype "passive"))
      (node (ref "U401") (pin "39") (pinfunction "PDSG_39") (pintype "passive"))
    )
    (net (code "27") (name "/BM_REG18") (class "Default")
      (node (ref "C413") (pin "2") (pinfunction "2_2") (pintype "passive"))
      (node (ref "C414") (pin "2") (pinfunction "2_2") (pintype "passive"))
      (node (ref "U401") (pin "24") (pinfunction "REG18_24") (pintype "power_in"))
    )
    (net (code "28") (name "/BM_REGIN") (class "Default")
      (node (ref "C415") (pin "2") (pinfunction "2_2") (pintype "passive"))
      (node (ref "Q401") (pin "3") (pinfunction "E_3") (pintype "passive"))
      (node (ref "U401") (pin "36") (pinfunction "REGIN_36") (pintype "passive"))
    )
    (net (code "29") (name "/BM_RST_SHUT") (class "Default")
      (node (ref "U401") (pin "33") (pinfunction "RST_SHUT_33") (pintype "passive"))
    )
    (net (code "30") (name "/BM_SCL") (class "Default")
      (node (ref "D401") (pin "1") (pinfunction "1_1") (pintype "passive"))
      (node (ref "R406") (pin "1") (pinfunction "1_1") (pintype "passive"))
      (node (ref "U401") (pin "26") (pinfunction "SCL_26") (pintype "input"))
    )
    (net (code "31") (name "/BM_SDA") (class "Default")
      (node (ref "D402") (pin "1") (pinfunction "1_1") (pintype "passive"))
      (node (ref "R407") (pin "1") (pinfunction "1_1") (pintype "passive"))
      (node (ref "U401") (pin "27") (pinfunction "SDA_27") (pintype "bidirectional"))
    )
    (net (code "32") (name "/BM_SRN") (class "Default")
      (node (ref "C407") (pin "2") (pinfunction "2_2") (pintype "passive"))
      (node (ref "C408") (pin "2") (pinfunction "2_2") (pintype "passive"))
      (node (ref "C409") (pin "2") (pinfunction "2_2") (pintype "passive"))
      (node (ref "R409") (pin "2") (pinfunction "2_2") (pintype "passive"))
      (node (ref "U401") (pin "20") (pinfunction "SRN_20") (pintype "passive"))
    )
    (net (code "33") (name "/BM_SRP") (class "Default")
      (node (ref "C406") (pin "2") (pinfunction "2_2") (pintype "passive"))
      (node (ref "C407") (pin "1") (pinfunction "1_1") (pintype "passive"))
      (node (ref "C408") (pin "1") (pinfunction "1_1") (pintype "passive"))
      (node (ref "R408") (pin "2") (pinfunction "2_2") (pintype "passive"))
      (node (ref "U401") (pin "18") (pinfunction "SRP_18") (pintype "passive"))
    )
    (net (code "34") (name "/BM_TS1") (class "Default")
      (node (ref "J402") (pin "1") (pinfunction "1_1") (pintype "passive"))
      (node (ref "U401") (pin "21") (pinfunction "TS1_21") (pintype "passive"))
    )
    (net (code "35") (name "/BM_TS1_R") (class "Default")
      (node (ref "J402") (pin "2") (pinfunction "2_2") (pintype "passive"))
      (node (ref "R434") (pin "2") (pinfunction "2_2") (pintype "passive"))
    )
    (net (code "36") (name "/BM_TS2") (class "Default")
      (node (ref "J401") (pin "1") (pinfunction "1_1") (pintype "passive"))
      (node (ref "U401") (pin "22") (pinfunction "TS2_22") (pintype "passive"))
    )
    (net (code "37") (name "/BM_TS2_R") (class "Default")
      (node (ref "J401") (pin "2") (pinfunction "2_2") (pintype "passive"))
      (node (ref "R412") (pin "2") (pinfunction "2_2") (pintype "passive"))
    )
    (net (code "38") (name "/BM_TS3") (class "Default")
      (node (ref "J403") (pin "1") (pinfunction "1_1") (pintype "passive"))
      (node (ref "U401") (pin "23") (pinfunction "TS3_23") (pintype "passive"))
    )
    (net (code "39") (name "/BM_TS3_R") (class "Default")
      (node (ref "J403") (pin "2") (pinfunction "2_2") (pintype "passive"))
      (node (ref "R435") (pin "2") (pinfunction "2_2") (pintype "passive"))
    )
    (net (code "40") (name "/BM_VC0") (class "Default")
      (node (ref "C404") (pin "2") (pinfunction "2_2") (pintype "passive"))
      (node (ref "R405") (pin "2") (pinfunction "2_2") (pintype "passive"))
      (node (ref "U401") (pin "16") (pinfunction "VC0_16") (pintype "input"))
    )
    (net (code "41") (name "/BM_VC1") (class "Default")
      (node (ref "C403") (pin "1") (pinfunction "1_1") (pintype "passive"))
      (node (ref "C405") (pin "2") (pinfunction "2_2") (pintype "passive"))
      (node (ref "R404") (pin "2") (pinfunction "2_2") (pintype "passive"))
      (node (ref "U401") (pin "15") (pinfunction "VC1_15") (pintype "input"))
    )
    (net (code "42") (name "/BM_VC2") (class "Default")
      (node (ref "C402") (pin "1") (pinfunction "1_1") (pintype "passive"))
      (node (ref "C403") (pin "2") (pinfunction "2_2") (pintype "passive"))
      (node (ref "R403") (pin "2") (pinfunction "2_2") (pintype "passive"))
      (node (ref "U401") (pin "14") (pinfunction "VC2_14") (pintype "input"))
    )
    (net (code "43") (name "/BM_VC9") (class "Default")
      (node (ref "C401") (pin "1") (pinfunction "1_1") (pintype "passive"))
      (node (ref "C402") (pin "2") (pinfunction "2_2") (pintype "passive"))
      (node (ref "R402") (pin "2") (pinfunction "2_2") (pintype "passive"))
      (node (ref "U401") (pin "10") (pinfunction "VC5_10") (pintype "input"))
      (node (ref "U401") (pin "12") (pinfunction "VC4_12") (pintype "input"))
      (node (ref "U401") (pin "13") (pinfunction "VC3_13") (pintype "input"))
      (node (ref "U401") (pin "2") (pinfunction "VC9_2") (pintype "input"))
      (node (ref "U401") (pin "4") (pinfunction "VC8_4") (pintype "input"))
      (node (ref "U401") (pin "6") (pinfunction "VC7_6") (pintype "input"))
      (node (ref "U401") (pin "8") (pinfunction "VC6_8") (pintype "input"))
    )
    (net (code "44") (name "/BM_VC10") (class "Default")
      (node (ref "C401") (pin "2") (pinfunction "2_2") (pintype "passive"))
      (node (ref "R401") (pin "2") (pinfunction "2_2") (pintype "passive"))
      (node (ref "U401") (pin "48") (pinfunction "VC10_48") (pintype "input"))
    )
    (net (code "45") (name "/C_GATE") (class "Default")
      (node (ref "D405") (pin "1") (pinfunction "K_1") (pintype "passive"))
      (node (ref "Q404") (pin "4") (pinfunction "G_4") (pintype "passive"))
      (node (ref "R418") (pin "1") (pinfunction "1_1") (pintype "passive"))
      (node (ref "R419") (pin "2") (pinfunction "2_2") (pintype "passive"))
    )
    (net (code "46") (name "/D_GATE") (class "Default")
      (node (ref "D406") (pin "1") (pinfunction "K_1") (pintype "passive"))
      (node (ref "Q405") (pin "4") (pinfunction "G_4") (pintype "passive"))
      (node (ref "Q406") (pin "3") (pinfunction "D_3") (pintype "passive"))
      (node (ref "R423") (pin "1") (pinfunction "1_1") (pintype "passive"))
      (node (ref "R424") (pin "2") (pinfunction "2_2") (pintype "passive"))
      (node (ref "R425") (pin "2") (pinfunction "2_2") (pintype "passive"))
    )
    (net (code "47") (name "/D_GATE_D") (class "Default")
      (node (ref "D407") (pin "1") (pinfunction "A_1") (pintype "passive"))
      (node (ref "R425") (pin "1") (pinfunction "1_1") (pintype "passive"))
    )
    (net (code "48") (name "/D_GATE_R") (class "Default")
      (node (ref "R424") (pin "1") (pinfunction "1_1") (pintype "passive"))
      (node (ref "R426") (pin "2") (pinfunction "2_2") (pintype "passive"))
    )
    (net (code "49") (name "/FET_CD") (class "Default")
      (node (ref "D404") (pin "2") (pinfunction "A_2") (pintype "passive"))
      (node (ref "Q402") (pin "2") (pinfunction "SOURCE_2") (pintype "passive"))
      (node (ref "Q403") (pin "2") (pinfunction "SOURCE_2") (pintype "passive"))
      (node (ref "Q404") (pin "5-6-7-8") (pinfunction "D_5-6-7-8") (pintype "passive"))
      (node (ref "Q405") (pin "5-6-7-8") (pinfunction "D_5-6-7-8") (pintype "passive"))
      (node (ref "R417") (pin "2") (pinfunction "2_2") (pintype "passive"))
      (node (ref "R420") (pin "2") (pinfunction "2_2") (pintype "passive"))
    )
    (net (code "50") (name "/MXC_P") (class "Default")
      (node (ref "D403") (pin "2") (pinfunction "A_2") (pintype "passive"))
      (node (ref "F401") (pin "1") (pinfunction "1_1") (pintype "passive"))
    )
    (net (code "51") (name "/MXC_P_D") (class "Default")
      (node (ref "D403") (pin "1") (pinfunction "C_1") (pintype "passive"))
      (node (ref "R411") (pin "1") (pinfunction "1_1") (pintype "passive"))
    )
    (net (code "52") (name "/MXC_P_F") (class "Default")
      (node (ref "C418") (pin "1") (pinfunction "1_1") (pintype "passive"))
      (node (ref "D405") (pin "2") (pinfunction "A_2") (pintype "passive"))
      (node (ref "F401") (pin "2") (pinfunction "2_2") (pintype "passive"))
      (node (ref "Q404") (pin "1") (pinfunction "S_1") (pintype "passive"))
      (node (ref "Q404") (pin "2") (pinfunction "S_2") (pintype "passive"))
      (node (ref "Q404") (pin "3") (pinfunction "S_3") (pintype "passive"))
      (node (ref "R415") (pin "1") (pinfunction "1_1") (pintype "passive"))
      (node (ref "R418") (pin "2") (pinfunction "2_2") (pintype "passive"))
    )
    (net (code "53") (name "/P_C_DRAIN") (class "Default")
      (node (ref "Q402") (pin "3") (pinfunction "DRAIN_3") (pintype "passive"))
      (node (ref "R415") (pin "2") (pinfunction "2_2") (pintype "passive"))
    )
    (net (code "54") (name "/P_C_GATE") (class "Default")
      (node (ref "Q402") (pin "1") (pinfunction "GATE_1") (pintype "passive"))
      (node (ref "R416") (pin "1") (pinfunction "1_1") (pintype "passive"))
      (node (ref "R417") (pin "1") (pinfunction "1_1") (pintype "passive"))
    )
    (net (code "55") (name "/P_D_DRAIN") (class "Default")
      (node (ref "Q403") (pin "3") (pinfunction "DRAIN_3") (pintype "passive"))
      (node (ref "R421") (pin "1") (pinfunction "1_1") (pintype "passive"))
    )
    (net (code "56") (name "/P_D_GATE") (class "Default")
      (node (ref "Q403") (pin "1") (pinfunction "GATE_1") (pintype "passive"))
      (node (ref "R420") (pin "1") (pinfunction "1_1") (pintype "passive"))
      (node (ref "R422") (pin "2") (pinfunction "2_2") (pintype "passive"))
    )
    (net (code "57") (name "/REV_PROTECT_GATE") (class "Default")
      (node (ref "D409") (pin "1") (pinfunction "K_1") (pintype "passive"))
      (node (ref "Q406") (pin "1") (pinfunction "G_1") (pintype "passive"))
      (node (ref "R427") (pin "1") (pinfunction "1_1") (pintype "passive"))
      (node (ref "R428") (pin "2") (pinfunction "2_2") (pintype "passive"))
    )
    (net (code "58") (name "/REV_PROTECT_RD") (class "Default")
      (node (ref "D410") (pin "2") (pinfunction "K_2") (pintype "passive"))
      (node (ref "R428") (pin "1") (pinfunction "1_1") (pintype "passive"))
    )
    (net (code "59") (name "BM_REG1") (class "Default")
      (node (ref "C412") (pin "1") (pinfunction "1_1") (pintype "passive"))
      (node (ref "R406") (pin "2") (pinfunction "2_2") (pintype "passive"))
      (node (ref "R407") (pin "2") (pinfunction "2_2") (pintype "passive"))
      (node (ref "R433") (pin "2") (pinfunction "2_2") (pintype "passive"))
      (node (ref "U401") (pin "35") (pinfunction "REG1_35") (pintype "passive"))
    )
    (net (code "60") (name "GND") (class "Default")
      (node (ref "C421") (pin "1") (pinfunction "1_1") (pintype "passive"))
      (node (ref "D401") (pin "2") (pinfunction "2_2") (pintype "passive"))
      (node (ref "D402") (pin "2") (pinfunction "2_2") (pintype "passive"))
      (node (ref "D410") (pin "1") (pinfunction "A_1") (pintype "passive"))
      (node (ref "R409") (pin "1") (pinfunction "1_1") (pintype "passive"))
      (node (ref "R410") (pin "2") (pinfunction "2_2") (pintype "passive"))
    )
    (net (code "61") (name "VSS") (class "Default")
      (node (ref "C404") (pin "1") (pinfunction "1_1") (pintype "passive"))
      (node (ref "C405") (pin "1") (pinfunction "1_1") (pintype "passive"))
      (node (ref "C406") (pin "1") (pinfunction "1_1") (pintype "passive"))
      (node (ref "C409") (pin "1") (pinfunction "1_1") (pintype "passive"))
      (node (ref "C410") (pin "2") (pinfunction "2_2") (pintype "passive"))
      (node (ref "C411") (pin "1") (pinfunction "1_1") (pintype "passive"))
      (node (ref "C412") (pin "2") (pinfunction "2_2") (pintype "passive"))
      (node (ref "C413") (pin "1") (pinfunction "1_1") (pintype "passive"))
      (node (ref "C414") (pin "1") (pinfunction "1_1") (pintype "passive"))
      (node (ref "C415") (pin "1") (pinfunction "1_1") (pintype "passive"))
      (node (ref "C416") (pin "2") (pinfunction "2_2") (pintype "passive"))
      (node (ref "D408") (pin "1") (pinfunction "A_1") (pintype "passive"))
      (node (ref "D411") (pin "1") (pinfunction "A_1") (pintype "passive"))
      (node (ref "D412") (pin "1") (pinfunction "A_1") (pintype "passive"))
      (node (ref "R408") (pin "1") (pinfunction "1_1") (pintype "passive"))
      (node (ref "R410") (pin "1") (pinfunction "1_1") (pintype "passive"))
      (node (ref "R412") (pin "1") (pinfunction "1_1") (pintype "passive"))
      (node (ref "R414") (pin "1") (pinfunction "1_1") (pintype "passive"))
      (node (ref "R434") (pin "1") (pinfunction "1_1") (pintype "passive"))
      (node (ref "R435") (pin "1") (pinfunction "1_1") (pintype "passive"))
      (node (ref "U401") (pin "17") (pinfunction "VSS_17") (pintype "power_in"))
    )
    (net (code "62") (name "unconnected-(U401-FUSE-Pad38)") (class "Default")
      (node (ref "U401") (pin "38") (pinfunction "FUSE_38") (pintype "passive+no_connect"))
    )
    (net (code "63") (name "unconnected-(U401-HDQ-Pad28)") (class "Default")
      (node (ref "U401") (pin "28") (pinfunction "HDQ_28") (pintype "passive+no_connect"))
    )
    (net (code "64") (name "unconnected-(U401-NC-Pad1)") (class "Default")
      (node (ref "U401") (pin "1") (pinfunction "NC_1") (pintype "passive+no_connect"))
    )
    (net (code "65") (name "unconnected-(U401-NC-Pad3)") (class "Default")
      (node (ref "U401") (pin "3") (pinfunction "NC_3") (pintype "passive+no_connect"))
    )
    (net (code "66") (name "unconnected-(U401-NC-Pad5)") (class "Default")
      (node (ref "U401") (pin "5") (pinfunction "NC_5") (pintype "passive+no_connect"))
    )
    (net (code "67") (name "unconnected-(U401-NC-Pad7)") (class "Default")
      (node (ref "U401") (pin "7") (pinfunction "NC_7") (pintype "passive+no_connect"))
    )
    (net (code "68") (name "unconnected-(U401-NC-Pad9)") (class "Default")
      (node (ref "U401") (pin "9") (pinfunction "NC_9") (pintype "passive+no_connect"))
    )
    (net (code "69") (name "unconnected-(U401-NC-Pad11)") (class "Default")
      (node (ref "U401") (pin "11") (pinfunction "NC_11") (pintype "passive+no_connect"))
    )
    (net (code "70") (name "unconnected-(U401-NC-Pad19)") (class "Default")
      (node (ref "U401") (pin "19") (pinfunction "NC_19") (pintype "passive+no_connect"))
    )
    (net (code "71") (name "unconnected-(U401-NC-Pad44)") (class "Default")
      (node (ref "U401") (pin "44") (pinfunction "NC_44") (pintype "passive+no_connect"))
    )
    (net (code "72") (name "unconnected-(U401-REG2-Pad34)") (class "Default")
      (node (ref "U401") (pin "34") (pinfunction "REG2_34") (pintype "passive+no_connect"))
    )
  )
)
